# Pro-Mini-ICSP-FTDI.net
KiCad netlist of a schematic drawn in EAGLE
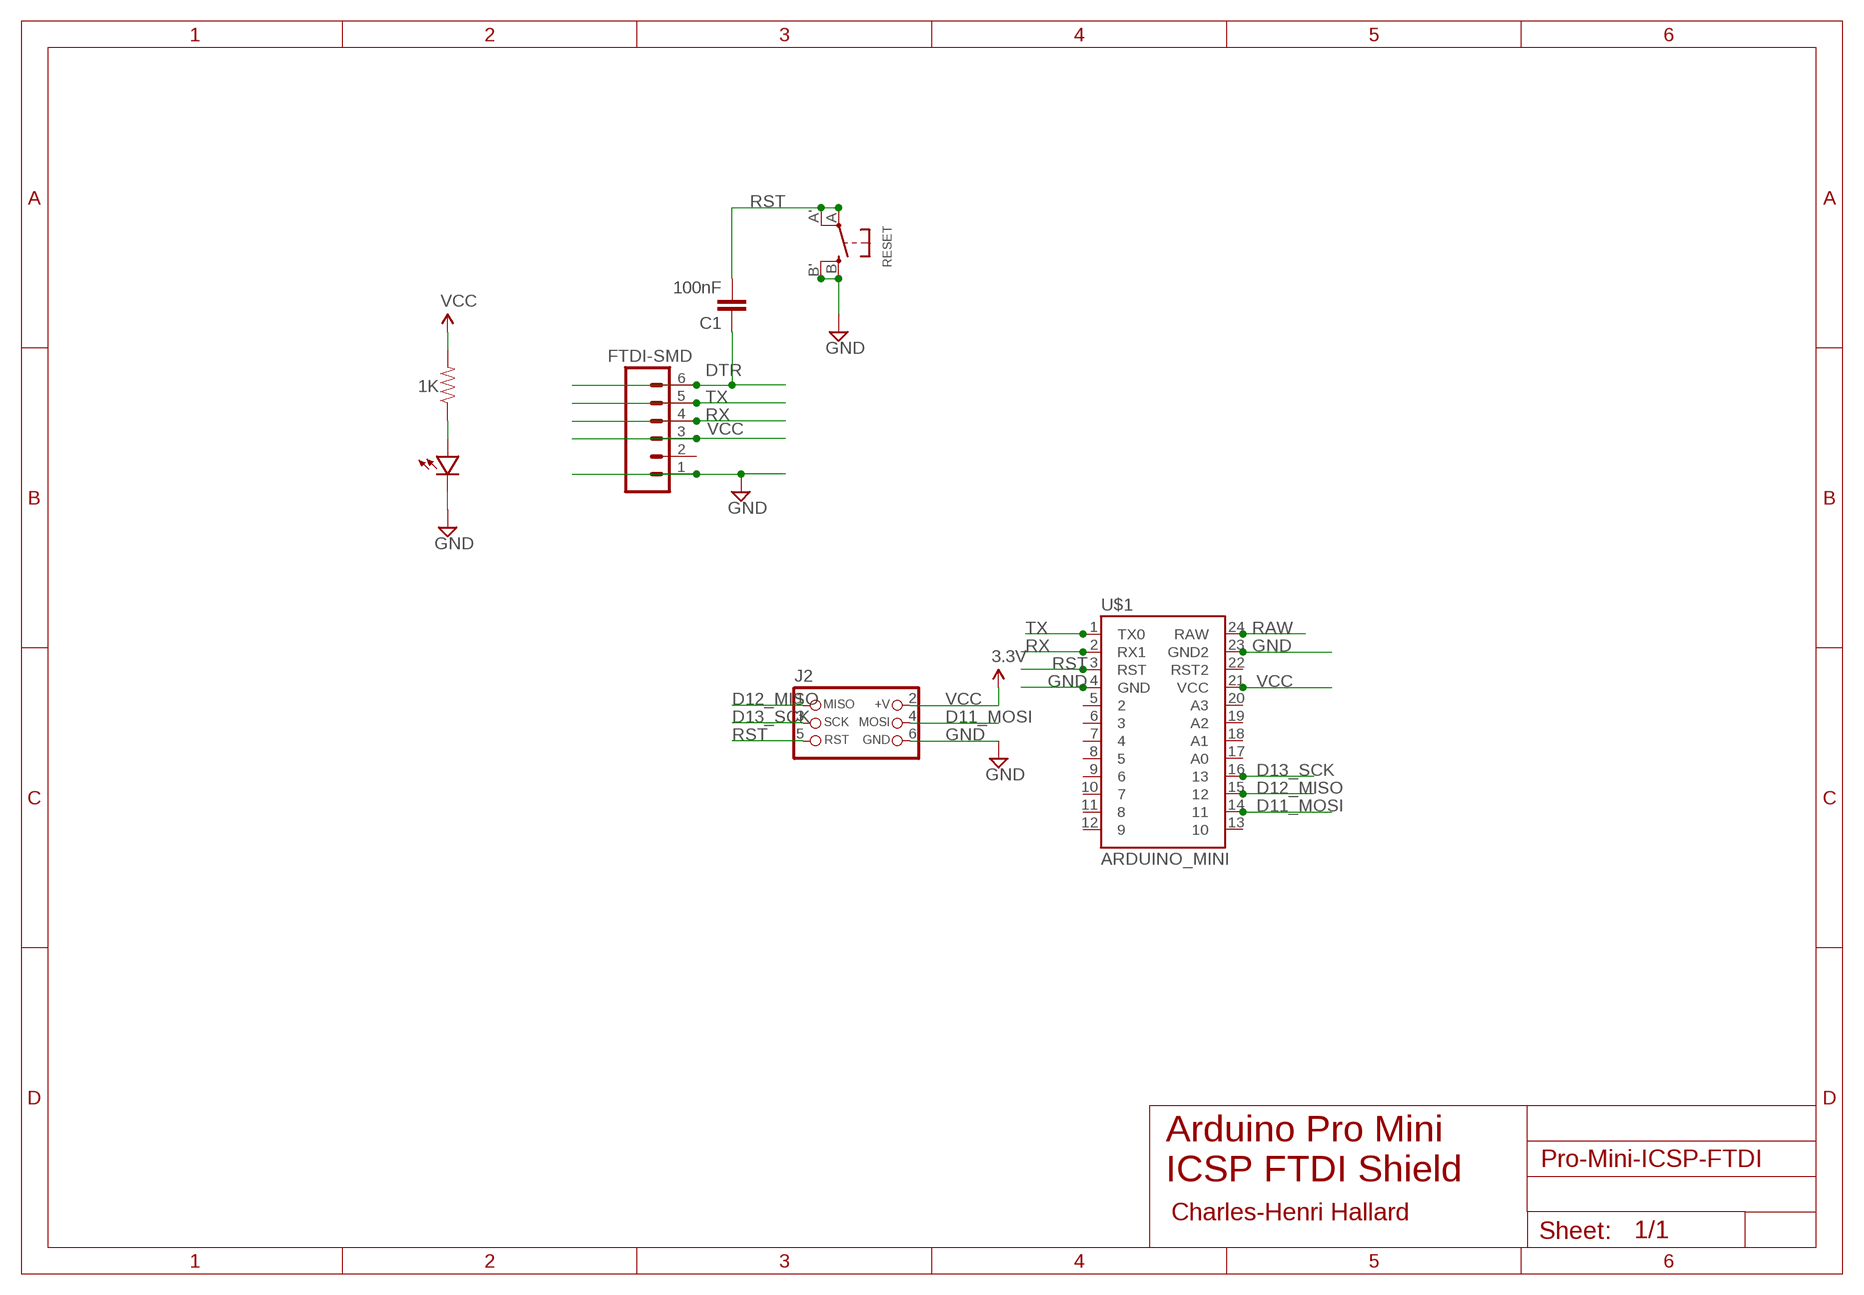
[diagram p0: schematic, sheet 1]

(export (version "E")
  (design (tool "Eeschema 10.0.6"))
  (components
    (comp (ref "C1")
      (value "100nF")
      (footprint "eagle-import:0805-CAP")
      (libsource (lib "eagle-import") (part "CAP0805-CAP"))
    )
    (comp (ref "FTDI-SMD")
      (value "SMD")
      (footprint "eagle-import:1X06")
      (libsource (lib "eagle-import") (part "M06SIP"))
    )
    (comp (ref "J2")
      (value "CON_HEADER_PRG_AVR_ICSP-PTH")
      (footprint "eagle-import:HEADER_PRG_2X03")
      (libsource (lib "eagle-import") (part "CON_HEADER_PRG_AVR_ICSP-PTH"))
    )
    (comp (ref "R1")
      (value "1K")
      (footprint "eagle-import:0805-RES")
      (libsource (lib "eagle-import") (part "RESISTOR0805-RES"))
    )
    (comp (ref "RESET")
      (value "SWITCH_TACT_SMT")
      (footprint "eagle-import:EVQ-Q2")
      (libsource (lib "eagle-import") (part "SWITCH_TACT_SMT"))
    )
    (comp (ref "U$1")
      (value "ARDUINO_MINI")
      (footprint "eagle-import:ARDUINO_MINI")
      (libsource (lib "eagle-import") (part "ARDUINO_MINI"))
    )
    (comp (ref "U$2")
      (value "LED0805")
      (footprint "eagle-import:0805-LED")
      (libsource (lib "eagle-import") (part "LED0805"))
    )
  )
  (nets
    (net (code "1") (name "/D11_MOSI") (class "Default")
      (node (ref "J2") (pin "4") (pinfunction "MOSI_4") (pintype "passive"))
      (node (ref "U$1") (pin "14") (pinfunction "11_14") (pintype "bidirectional"))
    )
    (net (code "2") (name "/D12_MISO") (class "Default")
      (node (ref "J2") (pin "1") (pinfunction "MISO_1") (pintype "passive"))
      (node (ref "U$1") (pin "15") (pinfunction "12_15") (pintype "bidirectional"))
    )
    (net (code "3") (name "/D13_SCK") (class "Default")
      (node (ref "J2") (pin "3") (pinfunction "SCK_3") (pintype "passive"))
      (node (ref "U$1") (pin "16") (pinfunction "13_16") (pintype "bidirectional"))
    )
    (net (code "4") (name "/DTR") (class "Default")
      (node (ref "C1") (pin "1") (pinfunction "1_1") (pintype "passive"))
      (node (ref "FTDI-SMD") (pin "6") (pinfunction "6_6") (pintype "passive"))
    )
    (net (code "5") (name "/RAW") (class "Default")
      (node (ref "U$1") (pin "24") (pinfunction "RAW_24") (pintype "bidirectional"))
    )
    (net (code "6") (name "/RST") (class "Default")
      (node (ref "C1") (pin "2") (pinfunction "2_2") (pintype "passive"))
      (node (ref "J2") (pin "5") (pinfunction "RST_5") (pintype "passive"))
      (node (ref "RESET") (pin "A") (pinfunction "P_A") (pintype "passive"))
      (node (ref "RESET") (pin "A'") (pinfunction "P1_A'") (pintype "passive"))
      (node (ref "U$1") (pin "3") (pinfunction "RST_3") (pintype "bidirectional"))
    )
    (net (code "7") (name "/RX") (class "Default")
      (node (ref "FTDI-SMD") (pin "4") (pinfunction "4_4") (pintype "passive"))
      (node (ref "U$1") (pin "2") (pinfunction "RX1_2") (pintype "bidirectional"))
    )
    (net (code "8") (name "/TX") (class "Default")
      (node (ref "FTDI-SMD") (pin "5") (pinfunction "5_5") (pintype "passive"))
      (node (ref "U$1") (pin "1") (pinfunction "TX0_1") (pintype "bidirectional"))
    )
    (net (code "9") (name "3.3V") (class "Default")
      (node (ref "FTDI-SMD") (pin "3") (pinfunction "3_3") (pintype "passive"))
      (node (ref "J2") (pin "2") (pinfunction "+V_2") (pintype "passive"))
      (node (ref "R1") (pin "2") (pinfunction "2_2") (pintype "passive"))
      (node (ref "U$1") (pin "21") (pinfunction "VCC_21") (pintype "bidirectional"))
    )
    (net (code "10") (name "GND") (class "Default")
      (node (ref "FTDI-SMD") (pin "1") (pinfunction "1_1") (pintype "passive"))
      (node (ref "J2") (pin "6") (pinfunction "GND_6") (pintype "passive"))
      (node (ref "RESET") (pin "B") (pinfunction "S_B") (pintype "passive"))
      (node (ref "RESET") (pin "B'") (pinfunction "S1_B'") (pintype "passive"))
      (node (ref "U$1") (pin "23") (pinfunction "GND2_23") (pintype "bidirectional"))
      (node (ref "U$1") (pin "4") (pinfunction "GND_4") (pintype "bidirectional"))
      (node (ref "U$2") (pin "MINUS") (pinfunction "MINUS_MINUS") (pintype "passive"))
    )
    (net (code "11") (name "Net-(R1-Pad1)") (class "Default")
      (node (ref "R1") (pin "1") (pinfunction "1_1") (pintype "passive"))
      (node (ref "U$2") (pin "PLUS") (pinfunction "PLUS_PLUS") (pintype "passive"))
    )
    (net (code "12") (name "unconnected-(FTDI-SMD-Pad2)") (class "Default")
      (node (ref "FTDI-SMD") (pin "2") (pinfunction "2_2") (pintype "passive"))
    )
    (net (code "13") (name "unconnected-(U$1-2-Pad5)") (class "Default")
      (node (ref "U$1") (pin "5") (pinfunction "2_5") (pintype "bidirectional"))
    )
    (net (code "14") (name "unconnected-(U$1-3-Pad6)") (class "Default")
      (node (ref "U$1") (pin "6") (pinfunction "3_6") (pintype "bidirectional"))
    )
    (net (code "15") (name "unconnected-(U$1-4-Pad7)") (class "Default")
      (node (ref "U$1") (pin "7") (pinfunction "4_7") (pintype "bidirectional"))
    )
    (net (code "16") (name "unconnected-(U$1-5-Pad8)") (class "Default")
      (node (ref "U$1") (pin "8") (pinfunction "5_8") (pintype "bidirectional"))
    )
    (net (code "17") (name "unconnected-(U$1-6-Pad9)") (class "Default")
      (node (ref "U$1") (pin "9") (pinfunction "6_9") (pintype "bidirectional"))
    )
    (net (code "18") (name "unconnected-(U$1-7-Pad10)") (class "Default")
      (node (ref "U$1") (pin "10") (pinfunction "7_10") (pintype "bidirectional"))
    )
    (net (code "19") (name "unconnected-(U$1-8-Pad11)") (class "Default")
      (node (ref "U$1") (pin "11") (pinfunction "8_11") (pintype "bidirectional"))
    )
    (net (code "20") (name "unconnected-(U$1-9-Pad12)") (class "Default")
      (node (ref "U$1") (pin "12") (pinfunction "9_12") (pintype "bidirectional"))
    )
    (net (code "21") (name "unconnected-(U$1-10-Pad13)") (class "Default")
      (node (ref "U$1") (pin "13") (pinfunction "10_13") (pintype "bidirectional"))
    )
    (net (code "22") (name "unconnected-(U$1-A0-Pad17)") (class "Default")
      (node (ref "U$1") (pin "17") (pinfunction "A0_17") (pintype "bidirectional"))
    )
    (net (code "23") (name "unconnected-(U$1-A1-Pad18)") (class "Default")
      (node (ref "U$1") (pin "18") (pinfunction "A1_18") (pintype "bidirectional"))
    )
    (net (code "24") (name "unconnected-(U$1-A2-Pad19)") (class "Default")
      (node (ref "U$1") (pin "19") (pinfunction "A2_19") (pintype "bidirectional"))
    )
    (net (code "25") (name "unconnected-(U$1-A3-Pad20)") (class "Default")
      (node (ref "U$1") (pin "20") (pinfunction "A3_20") (pintype "bidirectional"))
    )
    (net (code "26") (name "unconnected-(U$1-RST2-Pad22)") (class "Default")
      (node (ref "U$1") (pin "22") (pinfunction "RST2_22") (pintype "bidirectional"))
    )
  )
)
